# slave-basic.net
KiCad netlist of a schematic drawn in EAGLE
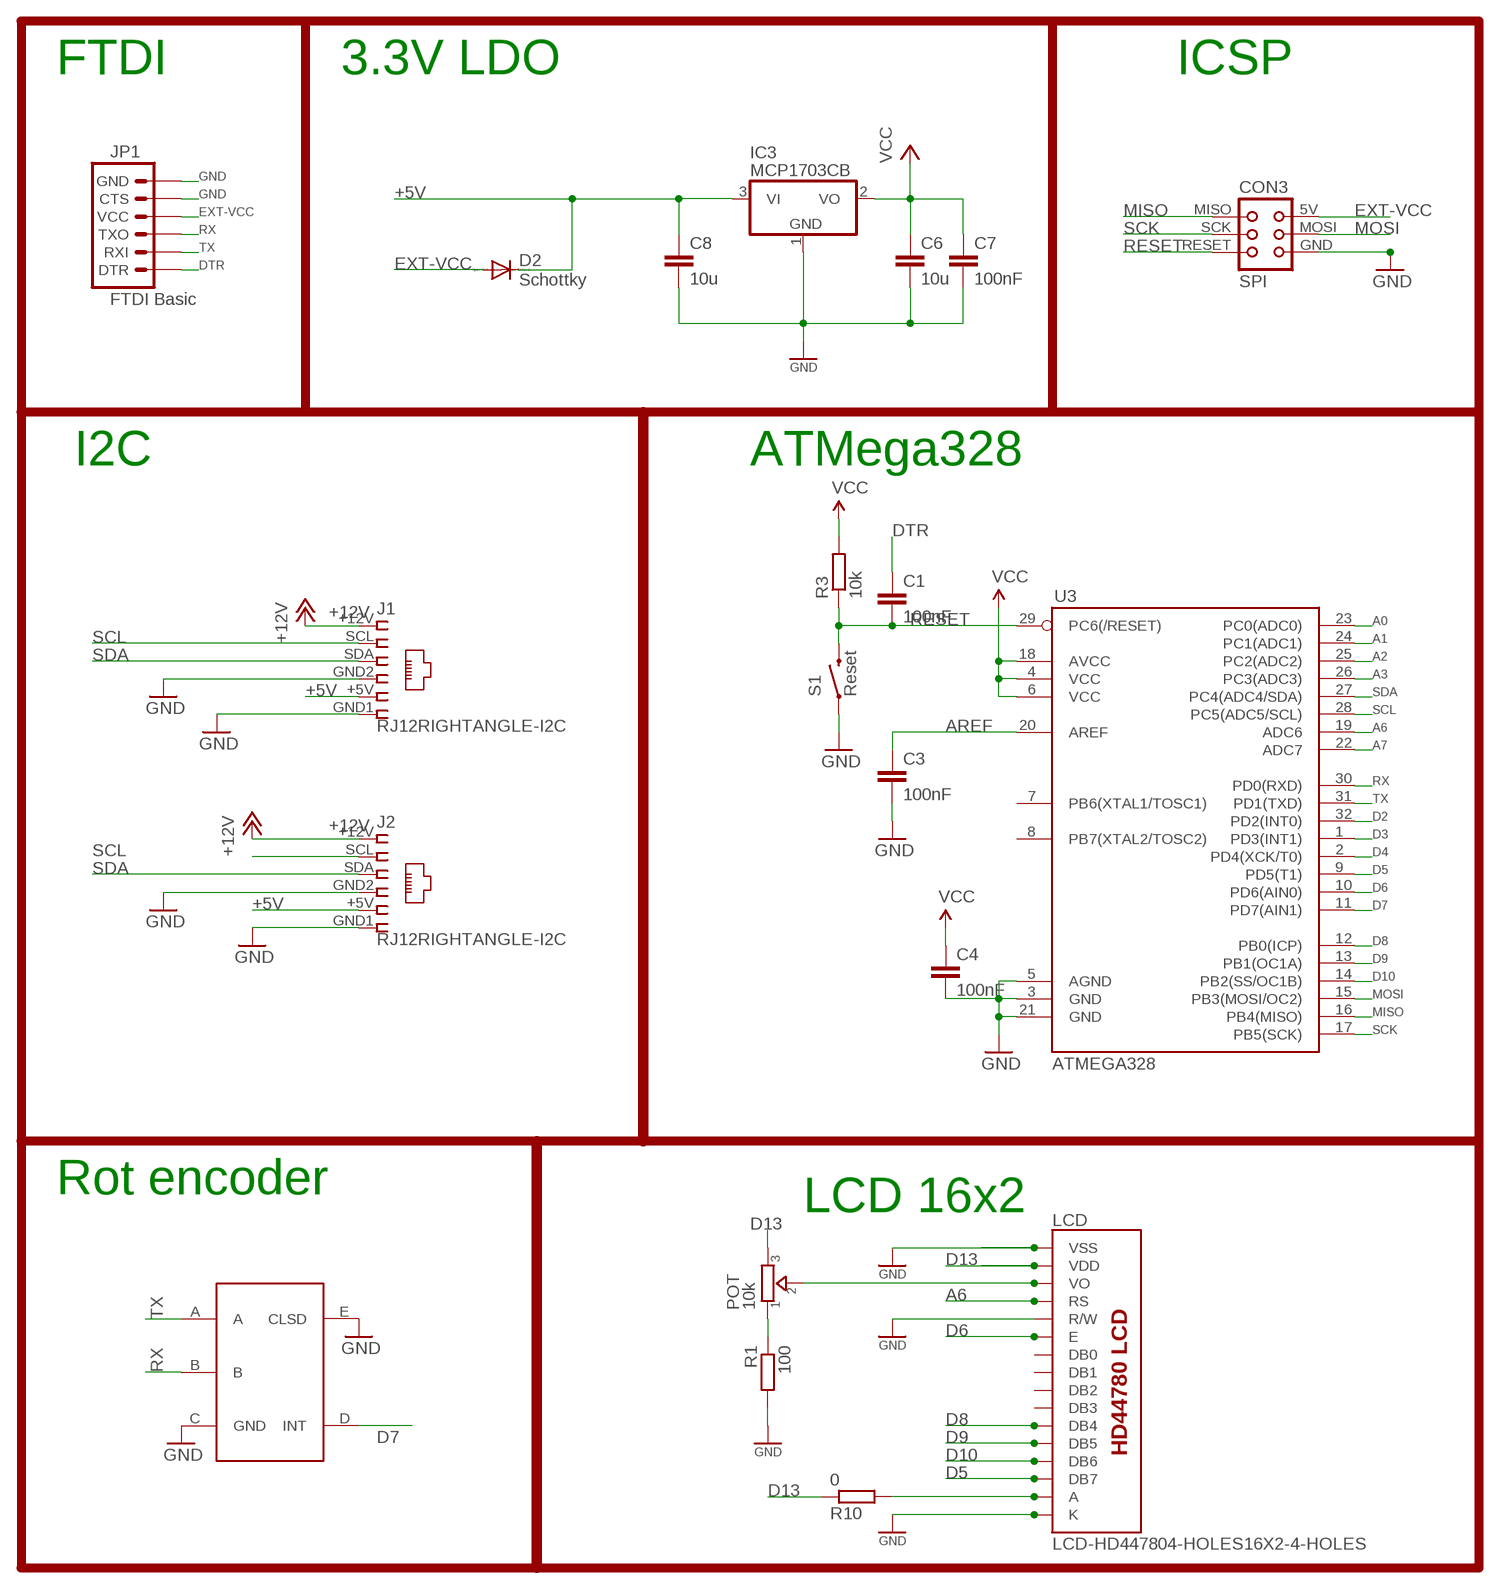
[diagram p0: schematic, sheet 1]

(export (version "E")
  (design (tool "Eeschema 10.0.6"))
  (components
    (comp (ref "C1")
      (value "100nF")
      (footprint "eagle-import:C0805K")
      (fields (field (name "MPN") "80-C1206C104K5R"))
      (libsource (lib "eagle-import") (part "C-EUC0805K"))
    )
    (comp (ref "C3")
      (value "100nF")
      (footprint "eagle-import:C0805K")
      (fields (field (name "MPN") "80-C1206C104K5R"))
      (libsource (lib "eagle-import") (part "C-EUC0805K"))
    )
    (comp (ref "C4")
      (value "100nF")
      (footprint "eagle-import:C0805K")
      (fields (field (name "MPN") "80-C1206C104K5R"))
      (libsource (lib "eagle-import") (part "C-EUC0805K"))
    )
    (comp (ref "C6")
      (value "10u")
      (footprint "eagle-import:C0805K")
      (fields (field (name "MPN") "77-VJ1206V106ZXQTBC"))
      (libsource (lib "eagle-import") (part "C-EUC0805K"))
    )
    (comp (ref "C7")
      (value "100nF")
      (footprint "eagle-import:C0805K")
      (fields (field (name "MPN") "80-C1206C104K5R"))
      (libsource (lib "eagle-import") (part "C-EUC0805K"))
    )
    (comp (ref "C8")
      (value "10u")
      (footprint "eagle-import:C0805K")
      (fields (field (name "MPN") "77-VJ1206V106ZXQTBC"))
      (libsource (lib "eagle-import") (part "C-EUC0805K"))
    )
    (comp (ref "CON3")
      (value "SPI")
      (footprint "eagle-import:TC2030-MCP")
      (libsource (lib "eagle-import") (part "TINYISPTAG"))
    )
    (comp (ref "D2")
      (value "Schottky")
      (footprint "eagle-import:SOD123")
      (fields (field (name "MPN") "621-1N5819HW-F"))
      (libsource (lib "eagle-import") (part "MBR0520LT"))
    )
    (comp (ref "IC3")
      (value "MCP1703CB")
      (footprint "eagle-import:SOT23")
      (libsource (lib "eagle-import") (part "MCP1703CB"))
    )
    (comp (ref "J1")
      (value "RJ12RIGHTANGLE-I2C")
      (footprint "eagle-import:RJ12-RIGHTANGLE-I2C")
      (libsource (lib "eagle-import") (part "RJ12RIGHTANGLE-I2C"))
    )
    (comp (ref "J2")
      (value "RJ12RIGHTANGLE-I2C")
      (footprint "eagle-import:RJ12-RIGHTANGLE-I2C")
      (libsource (lib "eagle-import") (part "RJ12RIGHTANGLE-I2C"))
    )
    (comp (ref "JP1")
      (value "FTDI Basic")
      (footprint "eagle-import:1X06")
      (libsource (lib "eagle-import") (part "ARDUINO_SERIAL_PROGRAMPTH"))
    )
    (comp (ref "LCD")
      (value "LCD-HD447804-HOLES16X2-4-HOLES")
      (footprint "eagle-import:LCD-16X2-4HOLES")
      (libsource (lib "eagle-import") (part "LCD-HD4478016X2-4-HOLES4-HOLES"))
    )
    (comp (ref "POT")
      (value "10k")
      (footprint "eagle-import:TRIMMER_3362P")
      (libsource (lib "eagle-import") (part "TRIMMER-3362P"))
    )
    (comp (ref "R1")
      (value "100")
      (footprint "eagle-import:R0805")
      (libsource (lib "eagle-import") (part "R-EU_R0805"))
    )
    (comp (ref "R3")
      (value "10k")
      (footprint "eagle-import:R0805")
      (libsource (lib "eagle-import") (part "R-EU_R0805"))
    )
    (comp (ref "R10")
      (value "0")
      (footprint "eagle-import:R0805")
      (libsource (lib "eagle-import") (part "rcl_334_R-EU_R0805"))
    )
    (comp (ref "S1")
      (value "Reset")
      (footprint "eagle-import:TACTILE-SWITCH-SMD-ALT01")
      (libsource (lib "eagle-import") (part "SWITCH-MOMENTARY-2SMD-ALT01"))
    )
    (comp (ref "U$1")
      (value "EC11E")
      (footprint "eagle-import:EC11E")
      (libsource (lib "eagle-import") (part "EC11E"))
    )
    (comp (ref "U3")
      (value "ATMEGA328")
      (footprint "eagle-import:TQFP32-08")
      (libsource (lib "eagle-import") (part "ATMEGA168"))
    )
  )
  (nets
    (net (code "1") (name "+12V") (class "Default")
      (node (ref "J1") (pin "+12V") (pinfunction "1_+12V") (pintype "bidirectional"))
      (node (ref "J2") (pin "+12V") (pinfunction "1_+12V") (pintype "bidirectional"))
    )
    (net (code "2") (name "/+5V") (class "Default")
      (node (ref "C8") (pin "1") (pinfunction "1_1") (pintype "passive"))
      (node (ref "D2") (pin "C") (pinfunction "C_C") (pintype "passive"))
      (node (ref "IC3") (pin "3") (pinfunction "VI_3") (pintype "input"))
      (node (ref "J1") (pin "+5V") (pinfunction "5_+5V") (pintype "bidirectional"))
      (node (ref "J2") (pin "+5V") (pinfunction "5_+5V") (pintype "bidirectional"))
    )
    (net (code "3") (name "/A0") (class "Default")
      (node (ref "U3") (pin "23") (pinfunction "PC0(ADC0)_23") (pintype "bidirectional"))
    )
    (net (code "4") (name "/A1") (class "Default")
      (node (ref "U3") (pin "24") (pinfunction "PC1(ADC1)_24") (pintype "bidirectional"))
    )
    (net (code "5") (name "/A2") (class "Default")
      (node (ref "U3") (pin "25") (pinfunction "PC2(ADC2)_25") (pintype "bidirectional"))
    )
    (net (code "6") (name "/A3") (class "Default")
      (node (ref "U3") (pin "26") (pinfunction "PC3(ADC3)_26") (pintype "bidirectional"))
    )
    (net (code "7") (name "/A6") (class "Default")
      (node (ref "LCD") (pin "4") (pinfunction "RS_4") (pintype "input"))
      (node (ref "U3") (pin "19") (pinfunction "ADC6_19") (pintype "bidirectional"))
    )
    (net (code "8") (name "/A7") (class "Default")
      (node (ref "U3") (pin "22") (pinfunction "ADC7_22") (pintype "bidirectional"))
    )
    (net (code "9") (name "/AREF") (class "Default")
      (node (ref "C3") (pin "1") (pinfunction "1_1") (pintype "passive"))
      (node (ref "U3") (pin "20") (pinfunction "AREF_20") (pintype "bidirectional"))
    )
    (net (code "10") (name "/D2") (class "Default")
      (node (ref "U3") (pin "32") (pinfunction "PD2(INT0)_32") (pintype "bidirectional"))
    )
    (net (code "11") (name "/D3") (class "Default")
      (node (ref "U3") (pin "1") (pinfunction "PD3(INT1)_1") (pintype "bidirectional"))
    )
    (net (code "12") (name "/D4") (class "Default")
      (node (ref "U3") (pin "2") (pinfunction "PD4(XCK/T0)_2") (pintype "bidirectional"))
    )
    (net (code "13") (name "/D5") (class "Default")
      (node (ref "LCD") (pin "14") (pinfunction "DB7_14") (pintype "bidirectional"))
      (node (ref "U3") (pin "9") (pinfunction "PD5(T1)_9") (pintype "bidirectional"))
    )
    (net (code "14") (name "/D6") (class "Default")
      (node (ref "LCD") (pin "6") (pinfunction "E_6") (pintype "input"))
      (node (ref "U3") (pin "10") (pinfunction "PD6(AIN0)_10") (pintype "bidirectional"))
    )
    (net (code "15") (name "/D7") (class "Default")
      (node (ref "U$1") (pin "D") (pinfunction "INT_D") (pintype "bidirectional"))
      (node (ref "U3") (pin "11") (pinfunction "PD7(AIN1)_11") (pintype "bidirectional"))
    )
    (net (code "16") (name "/D8") (class "Default")
      (node (ref "LCD") (pin "11") (pinfunction "DB4_11") (pintype "bidirectional"))
      (node (ref "U3") (pin "12") (pinfunction "PB0(ICP)_12") (pintype "bidirectional"))
    )
    (net (code "17") (name "/D9") (class "Default")
      (node (ref "LCD") (pin "12") (pinfunction "DB5_12") (pintype "bidirectional"))
      (node (ref "U3") (pin "13") (pinfunction "PB1(OC1A)_13") (pintype "bidirectional"))
    )
    (net (code "18") (name "/D10") (class "Default")
      (node (ref "LCD") (pin "13") (pinfunction "DB6_13") (pintype "bidirectional"))
      (node (ref "U3") (pin "14") (pinfunction "PB2(SS/OC1B)_14") (pintype "bidirectional"))
    )
    (net (code "19") (name "/D13") (class "Default")
      (node (ref "LCD") (pin "2") (pinfunction "VDD_2") (pintype "power_in"))
      (node (ref "POT") (pin "3") (pinfunction "3_3") (pintype "passive"))
      (node (ref "R10") (pin "1") (pinfunction "1_1") (pintype "passive"))
    )
    (net (code "20") (name "/DTR") (class "Default")
      (node (ref "C1") (pin "1") (pinfunction "1_1") (pintype "passive"))
      (node (ref "JP1") (pin "1") (pinfunction "DTR_1") (pintype "passive"))
    )
    (net (code "21") (name "/EXT-VCC") (class "Default")
      (node (ref "CON3") (pin "5V") (pinfunction "VCC_5V") (pintype "passive"))
      (node (ref "D2") (pin "A") (pinfunction "A_A") (pintype "passive"))
      (node (ref "JP1") (pin "4") (pinfunction "VCC_4") (pintype "passive"))
    )
    (net (code "22") (name "/MISO") (class "Default")
      (node (ref "CON3") (pin "MISO") (pinfunction "MISO_MISO") (pintype "passive"))
      (node (ref "U3") (pin "16") (pinfunction "PB4(MISO)_16") (pintype "bidirectional"))
    )
    (net (code "23") (name "/MOSI") (class "Default")
      (node (ref "CON3") (pin "MOSI") (pinfunction "MOSI_MOSI") (pintype "passive"))
      (node (ref "U3") (pin "15") (pinfunction "PB3(MOSI/OC2)_15") (pintype "bidirectional"))
    )
    (net (code "24") (name "/RESET") (class "Default")
      (node (ref "C1") (pin "2") (pinfunction "2_2") (pintype "passive"))
      (node (ref "CON3") (pin "RESET") (pinfunction "RESET_RESET") (pintype "passive"))
      (node (ref "R3") (pin "1") (pinfunction "1_1") (pintype "passive"))
      (node (ref "S1") (pin "3") (pinfunction "2_3") (pintype "passive"))
      (node (ref "S1") (pin "4") (pinfunction "2_4") (pintype "passive"))
      (node (ref "U3") (pin "29") (pinfunction "PC6(/RESET)_29") (pintype "bidirectional"))
    )
    (net (code "25") (name "/RX") (class "Default")
      (node (ref "JP1") (pin "3") (pinfunction "TXO_3") (pintype "passive"))
      (node (ref "U$1") (pin "B") (pinfunction "B_B") (pintype "bidirectional"))
      (node (ref "U3") (pin "30") (pinfunction "PD0(RXD)_30") (pintype "bidirectional"))
    )
    (net (code "26") (name "/SCK") (class "Default")
      (node (ref "CON3") (pin "SCK") (pinfunction "SCK_SCK") (pintype "passive"))
      (node (ref "U3") (pin "17") (pinfunction "PB5(SCK)_17") (pintype "bidirectional"))
    )
    (net (code "27") (name "/SCL") (class "Default")
      (node (ref "J1") (pin "SCL") (pinfunction "2_SCL") (pintype "bidirectional"))
      (node (ref "J2") (pin "SCL") (pinfunction "2_SCL") (pintype "bidirectional"))
      (node (ref "U3") (pin "28") (pinfunction "PC5(ADC5/SCL)_28") (pintype "bidirectional"))
    )
    (net (code "28") (name "/SDA") (class "Default")
      (node (ref "J1") (pin "SDA") (pinfunction "3_SDA") (pintype "bidirectional"))
      (node (ref "J2") (pin "SDA") (pinfunction "3_SDA") (pintype "bidirectional"))
      (node (ref "U3") (pin "27") (pinfunction "PC4(ADC4/SDA)_27") (pintype "bidirectional"))
    )
    (net (code "29") (name "/TX") (class "Default")
      (node (ref "JP1") (pin "2") (pinfunction "RXI_2") (pintype "passive"))
      (node (ref "U$1") (pin "A") (pinfunction "A_A") (pintype "bidirectional"))
      (node (ref "U3") (pin "31") (pinfunction "PD1(TXD)_31") (pintype "bidirectional"))
    )
    (net (code "30") (name "GND") (class "Default")
      (node (ref "C3") (pin "2") (pinfunction "2_2") (pintype "passive"))
      (node (ref "C4") (pin "2") (pinfunction "2_2") (pintype "passive"))
      (node (ref "C6") (pin "2") (pinfunction "2_2") (pintype "passive"))
      (node (ref "C7") (pin "2") (pinfunction "2_2") (pintype "passive"))
      (node (ref "C8") (pin "2") (pinfunction "2_2") (pintype "passive"))
      (node (ref "CON3") (pin "GND") (pinfunction "GND_GND") (pintype "passive"))
      (node (ref "IC3") (pin "1") (pinfunction "GND_1") (pintype "passive"))
      (node (ref "J1") (pin "GND1") (pinfunction "6_GND1") (pintype "bidirectional"))
      (node (ref "J1") (pin "GND2") (pinfunction "4_GND2") (pintype "bidirectional"))
      (node (ref "J2") (pin "GND1") (pinfunction "6_GND1") (pintype "bidirectional"))
      (node (ref "J2") (pin "GND2") (pinfunction "4_GND2") (pintype "bidirectional"))
      (node (ref "JP1") (pin "5") (pinfunction "CTS_5") (pintype "passive"))
      (node (ref "JP1") (pin "6") (pinfunction "GND_6") (pintype "passive"))
      (node (ref "LCD") (pin "1") (pinfunction "VSS_1") (pintype "power_in"))
      (node (ref "LCD") (pin "16") (pinfunction "K_16") (pintype "power_in"))
      (node (ref "LCD") (pin "5") (pinfunction "R/W_5") (pintype "input"))
      (node (ref "R1") (pin "2") (pinfunction "2_2") (pintype "passive"))
      (node (ref "S1") (pin "1") (pinfunction "1_1") (pintype "passive"))
      (node (ref "S1") (pin "2") (pinfunction "1_2") (pintype "passive"))
      (node (ref "U$1") (pin "C") (pinfunction "GND_C") (pintype "bidirectional"))
      (node (ref "U$1") (pin "E") (pinfunction "CLSD_E") (pintype "bidirectional"))
      (node (ref "U3") (pin "21") (pinfunction "GND_21") (pintype "bidirectional"))
      (node (ref "U3") (pin "3") (pinfunction "GND_3") (pintype "bidirectional"))
      (node (ref "U3") (pin "5") (pinfunction "AGND_5") (pintype "bidirectional"))
    )
    (net (code "31") (name "Net-(LCD-A)") (class "Default")
      (node (ref "LCD") (pin "15") (pinfunction "A_15") (pintype "power_in"))
      (node (ref "R10") (pin "2") (pinfunction "2_2") (pintype "passive"))
    )
    (net (code "32") (name "Net-(LCD-VO)") (class "Default")
      (node (ref "LCD") (pin "3") (pinfunction "VO_3") (pintype "bidirectional"))
      (node (ref "POT") (pin "2") (pinfunction "2_2") (pintype "passive"))
    )
    (net (code "33") (name "Net-(POT-Pad1)") (class "Default")
      (node (ref "POT") (pin "1") (pinfunction "1_1") (pintype "passive"))
      (node (ref "R1") (pin "1") (pinfunction "1_1") (pintype "passive"))
    )
    (net (code "34") (name "VCC") (class "Default")
      (node (ref "C4") (pin "1") (pinfunction "1_1") (pintype "passive"))
      (node (ref "C6") (pin "1") (pinfunction "1_1") (pintype "passive"))
      (node (ref "C7") (pin "1") (pinfunction "1_1") (pintype "passive"))
      (node (ref "IC3") (pin "2") (pinfunction "VO_2") (pintype "passive"))
      (node (ref "R3") (pin "2") (pinfunction "2_2") (pintype "passive"))
      (node (ref "U3") (pin "18") (pinfunction "AVCC_18") (pintype "bidirectional"))
      (node (ref "U3") (pin "4") (pinfunction "VCC_4") (pintype "bidirectional"))
      (node (ref "U3") (pin "6") (pinfunction "VCC_6") (pintype "bidirectional"))
    )
    (net (code "35") (name "unconnected-(LCD-DB0-Pad7)") (class "Default")
      (node (ref "LCD") (pin "7") (pinfunction "DB0_7") (pintype "bidirectional"))
    )
    (net (code "36") (name "unconnected-(LCD-DB1-Pad8)") (class "Default")
      (node (ref "LCD") (pin "8") (pinfunction "DB1_8") (pintype "bidirectional"))
    )
    (net (code "37") (name "unconnected-(LCD-DB2-Pad9)") (class "Default")
      (node (ref "LCD") (pin "9") (pinfunction "DB2_9") (pintype "bidirectional"))
    )
    (net (code "38") (name "unconnected-(LCD-DB3-Pad10)") (class "Default")
      (node (ref "LCD") (pin "10") (pinfunction "DB3_10") (pintype "bidirectional"))
    )
    (net (code "39") (name "unconnected-(U3-PB6(XTAL1{slash}TOSC1)-Pad7)") (class "Default")
      (node (ref "U3") (pin "7") (pinfunction "PB6(XTAL1/TOSC1)_7") (pintype "bidirectional"))
    )
    (net (code "40") (name "unconnected-(U3-PB7(XTAL2{slash}TOSC2)-Pad8)") (class "Default")
      (node (ref "U3") (pin "8") (pinfunction "PB7(XTAL2/TOSC2)_8") (pintype "bidirectional"))
    )
  )
)
